# design.net
KiCad netlist of a schematic drawn in Altium Designer
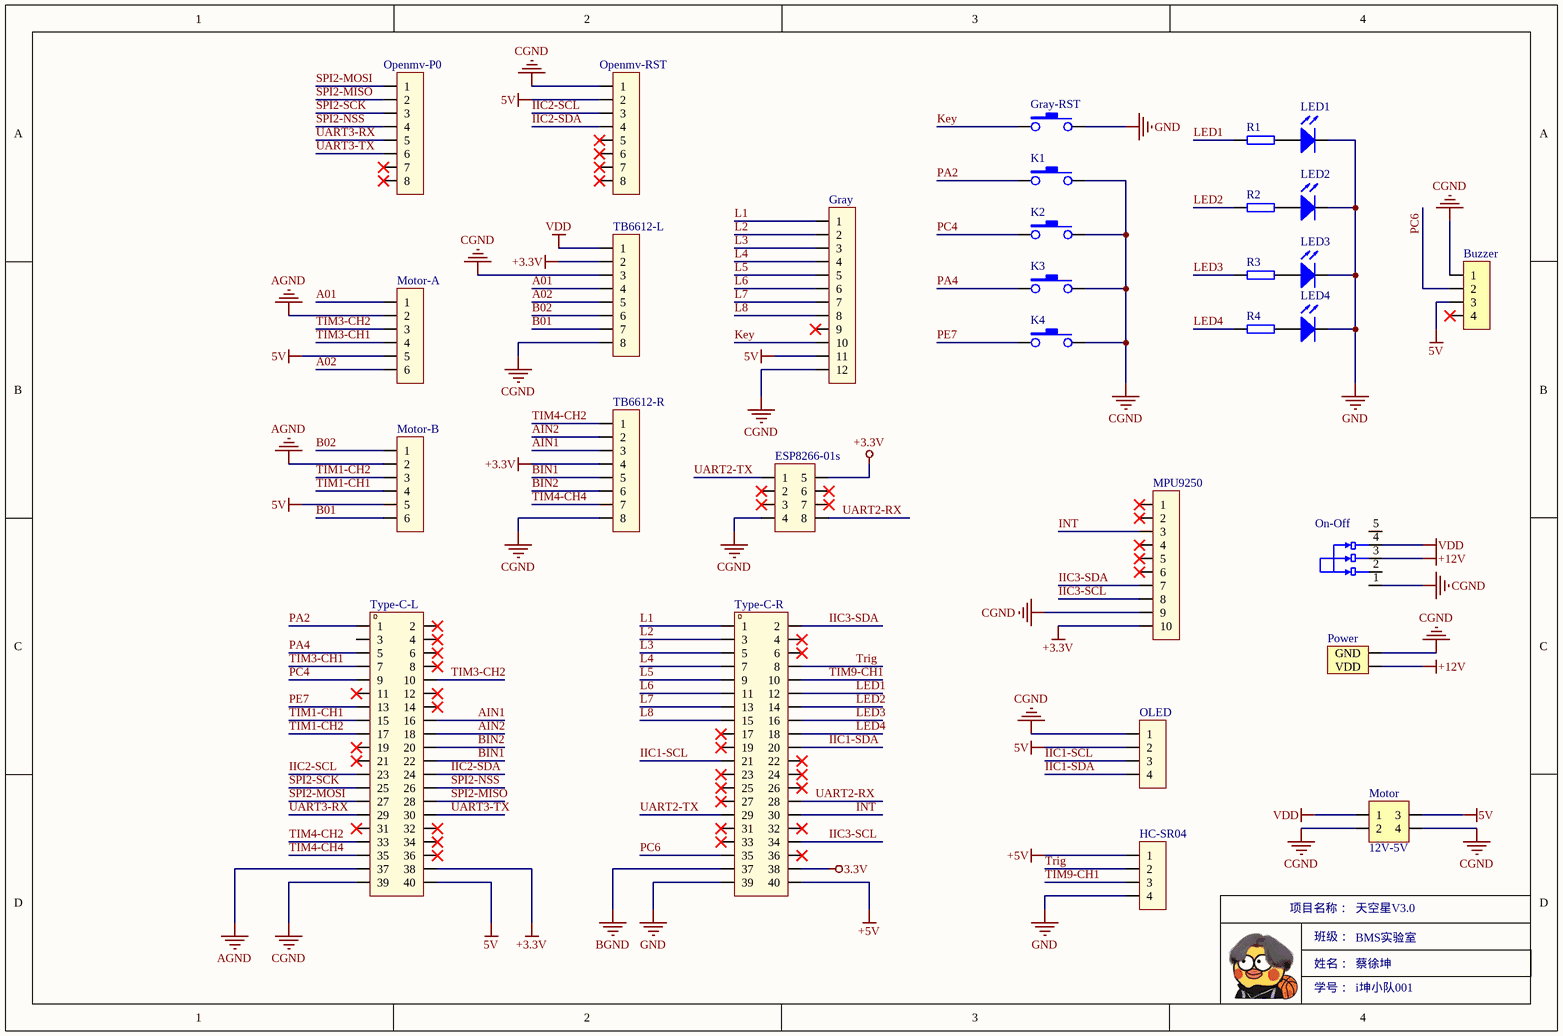
[diagram p0: 原理图.SchDoc]

(export (version "E")
  (design (tool "Eeschema 10.0.6"))
  (components
    (comp (ref "Buzzer")
      (value "~")
      (footprint "HDR2.54-M-LI-4P")
      (description "4P接插件")
      (fields (field (name "版权归属") "源创客"))
      (libsource (lib "HIST_SIE_E20240723") (part "Header 4"))
    )
    (comp (ref "ESP8266-01s")
      (value "~")
      (footprint "ESP8266-01s")
      (description "2*4P排母")
      (libsource (lib "WLOP_Yang") (part "2*4P"))
    )
    (comp (ref "Gray")
      (value "~")
      (footprint "XH2.54-1*12P")
      (description "1*12P排母")
      (libsource (lib "WLOP_Yang") (part "1*12P"))
    )
    (comp (ref "Gray-RST")
      (value "~")
      (footprint "贴片按键8mm")
      (description "12x12按键")
      (libsource (lib "HIST_SIE_E20240723") (part "Button-12X12-pin2"))
    )
    (comp (ref "HC-SR04")
      (value "~")
      (footprint "HC-SR04")
      (description "1*4P排母")
      (libsource (lib "WLOP_Yang") (part "1*4P"))
    )
    (comp (ref "K1")
      (value "~")
      (footprint "贴片按键8mm")
      (description "12x12按键")
      (libsource (lib "HIST_SIE_E20240723") (part "Button-12X12-pin2"))
    )
    (comp (ref "K2")
      (value "~")
      (footprint "贴片按键8mm")
      (description "12x12按键")
      (libsource (lib "HIST_SIE_E20240723") (part "Button-12X12-pin2"))
    )
    (comp (ref "K3")
      (value "~")
      (footprint "贴片按键8mm")
      (description "12x12按键")
      (libsource (lib "HIST_SIE_E20240723") (part "Button-12X12-pin2"))
    )
    (comp (ref "K4")
      (value "~")
      (footprint "贴片按键8mm")
      (description "12x12按键")
      (libsource (lib "HIST_SIE_E20240723") (part "Button-12X12-pin2"))
    )
    (comp (ref "LED1")
      (value "~")
      (footprint "LED-3mm")
      (description "普通M3发光二极管")
      (libsource (lib "HIST_SIE_E20240723") (part "D-LED-M3"))
    )
    (comp (ref "LED2")
      (value "~")
      (footprint "LED-3mm")
      (description "普通M3发光二极管")
      (libsource (lib "HIST_SIE_E20240723") (part "D-LED-M3"))
    )
    (comp (ref "LED3")
      (value "~")
      (footprint "LED-3mm")
      (description "普通M3发光二极管")
      (libsource (lib "HIST_SIE_E20240723") (part "D-LED-M3"))
    )
    (comp (ref "LED4")
      (value "~")
      (footprint "LED-3mm")
      (description "普通M3发光二极管")
      (libsource (lib "HIST_SIE_E20240723") (part "D-LED-M3"))
    )
    (comp (ref "Motor")
      (value "12V-5V")
      (footprint "12V-5V-Blue")
      (description "降压模块12V转5V")
      (libsource (lib "WLOP_Yang") (part "12V转5V"))
    )
    (comp (ref "Motor-A")
      (value "~")
      (footprint "XH2.54-1*6P直")
      (description "1*6P排母")
      (libsource (lib "WLOP_Yang") (part "1*6P"))
    )
    (comp (ref "Motor-B")
      (value "~")
      (footprint "XH2.54-1*6P直")
      (description "1*6P排母")
      (libsource (lib "WLOP_Yang") (part "1*6P"))
    )
    (comp (ref "MPU9250")
      (value "~")
      (footprint "MPU9250")
      (description "1*10P排母")
      (libsource (lib "WLOP_Yang") (part "1*10P"))
    )
    (comp (ref "OLED")
      (value "~")
      (footprint "OLED")
      (description "1*4P排母")
      (libsource (lib "WLOP_Yang") (part "1*4P"))
    )
    (comp (ref "On-Off")
      (value "~")
      (footprint "拨动开关")
      (description "2.54mm间距，拨动开关")
      (libsource (lib "WLOP_Yang") (part "拨动开关"))
    )
    (comp (ref "Openmv-P0")
      (value "~")
      (footprint "XH2.54-1*8P")
      (description "1*8P排母")
      (libsource (lib "WLOP_Yang") (part "1*8P"))
    )
    (comp (ref "Openmv-RST")
      (value "~")
      (footprint "XH2.54-1*8P")
      (description "1*8P排母")
      (libsource (lib "WLOP_Yang") (part "1*8P"))
    )
    (comp (ref "Power")
      (value "~")
      (footprint "立插端子-2P")
      (description "电源引脚")
      (libsource (lib "HIST_SIE_E20240723") (part "Power"))
    )
    (comp (ref "R1")
      (value "~")
      (footprint "120Ω")
      (description "1206")
      (libsource (lib "HIST_SIE_E20240723") (part "R-0805"))
    )
    (comp (ref "R2")
      (value "~")
      (footprint "120Ω")
      (description "1206")
      (libsource (lib "HIST_SIE_E20240723") (part "R-0805"))
    )
    (comp (ref "R3")
      (value "~")
      (footprint "120Ω")
      (description "1206")
      (libsource (lib "HIST_SIE_E20240723") (part "R-0805"))
    )
    (comp (ref "R4")
      (value "~")
      (footprint "120Ω")
      (description "1206")
      (libsource (lib "HIST_SIE_E20240723") (part "R-0805"))
    )
    (comp (ref "TB6612-L")
      (value "~")
      (footprint "排母-1*8P")
      (description "1*8P排母")
      (libsource (lib "WLOP_Yang") (part "1*8P"))
    )
    (comp (ref "TB6612-R")
      (value "~")
      (footprint "排母-1*8P")
      (description "1*8P排母")
      (libsource (lib "WLOP_Yang") (part "1*8P"))
    )
    (comp (ref "Type-C-L")
      (value "~")
      (footprint "排母2*20P")
      (description "2*20P排母")
      (libsource (lib "WLOP_Yang") (part "2*20P"))
    )
    (comp (ref "Type-C-R")
      (value "~")
      (footprint "排母2*20P")
      (description "2*20P排母")
      (libsource (lib "WLOP_Yang") (part "2*20P"))
    )
  )
  (nets
    (net (code "1") (name "+3.3V") (class "Default")
      (node (ref "ESP8266-01s") (pin "5") (pinfunction "5_5") (pintype "passive"))
      (node (ref "MPU9250") (pin "10") (pinfunction "10_10") (pintype "passive"))
      (node (ref "TB6612-L") (pin "2") (pinfunction "2_2") (pintype "passive"))
      (node (ref "TB6612-R") (pin "4") (pinfunction "4_4") (pintype "passive"))
      (node (ref "Type-C-L") (pin "38") (pinfunction "38_38") (pintype "passive"))
    )
    (net (code "2") (name "+5V") (class "Default")
      (node (ref "HC-SR04") (pin "1") (pinfunction "1_1") (pintype "passive"))
      (node (ref "Type-C-R") (pin "40") (pinfunction "40_40") (pintype "passive"))
    )
    (net (code "3") (name "+12V") (class "Default")
      (node (ref "On-Off") (pin "3") (pinfunction "3_3") (pintype "passive"))
      (node (ref "Power") (pin "1") (pinfunction "VDD_1") (pintype "passive"))
    )
    (net (code "4") (name "/A01") (class "Default")
      (node (ref "Motor-A") (pin "1") (pinfunction "1_1") (pintype "passive"))
      (node (ref "TB6612-L") (pin "4") (pinfunction "4_4") (pintype "passive"))
    )
    (net (code "5") (name "/A02") (class "Default")
      (node (ref "Motor-A") (pin "6") (pinfunction "6_6") (pintype "passive"))
      (node (ref "TB6612-L") (pin "5") (pinfunction "5_5") (pintype "passive"))
    )
    (net (code "6") (name "/AIN1") (class "Default")
      (node (ref "TB6612-R") (pin "3") (pinfunction "3_3") (pintype "passive"))
      (node (ref "Type-C-L") (pin "16") (pinfunction "16_16") (pintype "passive"))
    )
    (net (code "7") (name "/AIN2") (class "Default")
      (node (ref "TB6612-R") (pin "2") (pinfunction "2_2") (pintype "passive"))
      (node (ref "Type-C-L") (pin "18") (pinfunction "18_18") (pintype "passive"))
    )
    (net (code "8") (name "/B01") (class "Default")
      (node (ref "Motor-B") (pin "6") (pinfunction "6_6") (pintype "passive"))
      (node (ref "TB6612-L") (pin "7") (pinfunction "7_7") (pintype "passive"))
    )
    (net (code "9") (name "/B02") (class "Default")
      (node (ref "Motor-B") (pin "1") (pinfunction "1_1") (pintype "passive"))
      (node (ref "TB6612-L") (pin "6") (pinfunction "6_6") (pintype "passive"))
    )
    (net (code "10") (name "/BIN1") (class "Default")
      (node (ref "TB6612-R") (pin "5") (pinfunction "5_5") (pintype "passive"))
      (node (ref "Type-C-L") (pin "22") (pinfunction "22_22") (pintype "passive"))
    )
    (net (code "11") (name "/BIN2") (class "Default")
      (node (ref "TB6612-R") (pin "6") (pinfunction "6_6") (pintype "passive"))
      (node (ref "Type-C-L") (pin "20") (pinfunction "20_20") (pintype "passive"))
    )
    (net (code "12") (name "/IIC1-SCL") (class "Default")
      (node (ref "OLED") (pin "3") (pinfunction "3_3") (pintype "passive"))
      (node (ref "Type-C-R") (pin "21") (pinfunction "21_21") (pintype "passive"))
    )
    (net (code "13") (name "/IIC1-SDA") (class "Default")
      (node (ref "OLED") (pin "4") (pinfunction "4_4") (pintype "passive"))
      (node (ref "Type-C-R") (pin "20") (pinfunction "20_20") (pintype "passive"))
    )
    (net (code "14") (name "/IIC2-SCL") (class "Default")
      (node (ref "Openmv-RST") (pin "3") (pinfunction "3_3") (pintype "passive"))
      (node (ref "Type-C-L") (pin "23") (pinfunction "23_23") (pintype "passive"))
    )
    (net (code "15") (name "/IIC2-SDA") (class "Default")
      (node (ref "Openmv-RST") (pin "4") (pinfunction "4_4") (pintype "passive"))
      (node (ref "Type-C-L") (pin "24") (pinfunction "24_24") (pintype "passive"))
    )
    (net (code "16") (name "/IIC3-SCL") (class "Default")
      (node (ref "MPU9250") (pin "8") (pinfunction "8_8") (pintype "passive"))
      (node (ref "Type-C-R") (pin "34") (pinfunction "34_34") (pintype "passive"))
    )
    (net (code "17") (name "/IIC3-SDA") (class "Default")
      (node (ref "MPU9250") (pin "7") (pinfunction "7_7") (pintype "passive"))
      (node (ref "Type-C-R") (pin "2") (pinfunction "2_2") (pintype "passive"))
    )
    (net (code "18") (name "/INT") (class "Default")
      (node (ref "MPU9250") (pin "3") (pinfunction "3_3") (pintype "passive"))
      (node (ref "Type-C-R") (pin "30") (pinfunction "30_30") (pintype "passive"))
    )
    (net (code "19") (name "/Key") (class "Default")
      (node (ref "Gray") (pin "10") (pinfunction "10_10") (pintype "passive"))
      (node (ref "Gray-RST") (pin "1") (pintype "passive"))
    )
    (net (code "20") (name "/L1") (class "Default")
      (node (ref "Gray") (pin "1") (pinfunction "1_1") (pintype "passive"))
      (node (ref "Type-C-R") (pin "1") (pinfunction "1_1") (pintype "passive"))
    )
    (net (code "21") (name "/L2") (class "Default")
      (node (ref "Gray") (pin "2") (pinfunction "2_2") (pintype "passive"))
      (node (ref "Type-C-R") (pin "3") (pinfunction "3_3") (pintype "passive"))
    )
    (net (code "22") (name "/L3") (class "Default")
      (node (ref "Gray") (pin "3") (pinfunction "3_3") (pintype "passive"))
      (node (ref "Type-C-R") (pin "5") (pinfunction "5_5") (pintype "passive"))
    )
    (net (code "23") (name "/L4") (class "Default")
      (node (ref "Gray") (pin "4") (pinfunction "4_4") (pintype "passive"))
      (node (ref "Type-C-R") (pin "7") (pinfunction "7_7") (pintype "passive"))
    )
    (net (code "24") (name "/L5") (class "Default")
      (node (ref "Gray") (pin "5") (pinfunction "5_5") (pintype "passive"))
      (node (ref "Type-C-R") (pin "9") (pinfunction "9_9") (pintype "passive"))
    )
    (net (code "25") (name "/L6") (class "Default")
      (node (ref "Gray") (pin "6") (pinfunction "6_6") (pintype "passive"))
      (node (ref "Type-C-R") (pin "11") (pinfunction "11_11") (pintype "passive"))
    )
    (net (code "26") (name "/L7") (class "Default")
      (node (ref "Gray") (pin "7") (pinfunction "7_7") (pintype "passive"))
      (node (ref "Type-C-R") (pin "13") (pinfunction "13_13") (pintype "passive"))
    )
    (net (code "27") (name "/L8") (class "Default")
      (node (ref "Gray") (pin "8") (pinfunction "8_8") (pintype "passive"))
      (node (ref "Type-C-R") (pin "15") (pinfunction "15_15") (pintype "passive"))
    )
    (net (code "28") (name "/LED1") (class "Default")
      (node (ref "R1") (pin "1") (pintype "passive"))
      (node (ref "Type-C-R") (pin "12") (pinfunction "12_12") (pintype "passive"))
    )
    (net (code "29") (name "/LED2") (class "Default")
      (node (ref "R2") (pin "1") (pintype "passive"))
      (node (ref "Type-C-R") (pin "14") (pinfunction "14_14") (pintype "passive"))
    )
    (net (code "30") (name "/LED3") (class "Default")
      (node (ref "R3") (pin "1") (pintype "passive"))
      (node (ref "Type-C-R") (pin "16") (pinfunction "16_16") (pintype "passive"))
    )
    (net (code "31") (name "/LED4") (class "Default")
      (node (ref "R4") (pin "1") (pintype "passive"))
      (node (ref "Type-C-R") (pin "18") (pinfunction "18_18") (pintype "passive"))
    )
    (net (code "32") (name "/PA2") (class "Default")
      (node (ref "K1") (pin "1") (pintype "passive"))
      (node (ref "Type-C-L") (pin "1") (pinfunction "1_1") (pintype "passive"))
    )
    (net (code "33") (name "/PA4") (class "Default")
      (node (ref "K3") (pin "1") (pintype "passive"))
      (node (ref "Type-C-L") (pin "5") (pinfunction "5_5") (pintype "passive"))
    )
    (net (code "34") (name "/PC4") (class "Default")
      (node (ref "K2") (pin "1") (pintype "passive"))
      (node (ref "Type-C-L") (pin "9") (pinfunction "9_9") (pintype "passive"))
    )
    (net (code "35") (name "/PC6") (class "Default")
      (node (ref "Buzzer") (pin "2") (pinfunction "2_2") (pintype "passive"))
      (node (ref "Type-C-R") (pin "35") (pinfunction "35_35") (pintype "passive"))
    )
    (net (code "36") (name "/PE7") (class "Default")
      (node (ref "K4") (pin "1") (pintype "passive"))
      (node (ref "Type-C-L") (pin "13") (pinfunction "13_13") (pintype "passive"))
    )
    (net (code "37") (name "/SPI2-MISO") (class "Default")
      (node (ref "Openmv-P0") (pin "2") (pinfunction "2_2") (pintype "passive"))
      (node (ref "Type-C-L") (pin "28") (pinfunction "28_28") (pintype "passive"))
    )
    (net (code "38") (name "/SPI2-MOSI") (class "Default")
      (node (ref "Openmv-P0") (pin "1") (pinfunction "1_1") (pintype "passive"))
      (node (ref "Type-C-L") (pin "27") (pinfunction "27_27") (pintype "passive"))
    )
    (net (code "39") (name "/SPI2-NSS") (class "Default")
      (node (ref "Openmv-P0") (pin "4") (pinfunction "4_4") (pintype "passive"))
      (node (ref "Type-C-L") (pin "26") (pinfunction "26_26") (pintype "passive"))
    )
    (net (code "40") (name "/SPI2-SCK") (class "Default")
      (node (ref "Openmv-P0") (pin "3") (pinfunction "3_3") (pintype "passive"))
      (node (ref "Type-C-L") (pin "25") (pinfunction "25_25") (pintype "passive"))
    )
    (net (code "41") (name "/TIM1-CH1") (class "Default")
      (node (ref "Motor-B") (pin "4") (pinfunction "4_4") (pintype "passive"))
      (node (ref "Type-C-L") (pin "15") (pinfunction "15_15") (pintype "passive"))
    )
    (net (code "42") (name "/TIM1-CH2") (class "Default")
      (node (ref "Motor-B") (pin "3") (pinfunction "3_3") (pintype "passive"))
      (node (ref "Type-C-L") (pin "17") (pinfunction "17_17") (pintype "passive"))
    )
    (net (code "43") (name "/TIM3-CH1") (class "Default")
      (node (ref "Motor-A") (pin "4") (pinfunction "4_4") (pintype "passive"))
      (node (ref "Type-C-L") (pin "7") (pinfunction "7_7") (pintype "passive"))
    )
    (net (code "44") (name "/TIM3-CH2") (class "Default")
      (node (ref "Motor-A") (pin "3") (pinfunction "3_3") (pintype "passive"))
      (node (ref "Type-C-L") (pin "10") (pinfunction "10_10") (pintype "passive"))
    )
    (net (code "45") (name "/TIM4-CH2") (class "Default")
      (node (ref "TB6612-R") (pin "1") (pinfunction "1_1") (pintype "passive"))
      (node (ref "Type-C-L") (pin "33") (pinfunction "33_33") (pintype "passive"))
    )
    (net (code "46") (name "/TIM4-CH4") (class "Default")
      (node (ref "TB6612-R") (pin "7") (pinfunction "7_7") (pintype "passive"))
      (node (ref "Type-C-L") (pin "35") (pinfunction "35_35") (pintype "passive"))
    )
    (net (code "47") (name "/TIM9-CH1") (class "Default")
      (node (ref "HC-SR04") (pin "3") (pinfunction "3_3") (pintype "passive"))
      (node (ref "Type-C-R") (pin "10") (pinfunction "10_10") (pintype "passive"))
    )
    (net (code "48") (name "/Trig") (class "Default")
      (node (ref "HC-SR04") (pin "2") (pinfunction "2_2") (pintype "passive"))
      (node (ref "Type-C-R") (pin "8") (pinfunction "8_8") (pintype "passive"))
    )
    (net (code "49") (name "/UART2-RX") (class "Default")
      (node (ref "ESP8266-01s") (pin "8") (pinfunction "8_8") (pintype "passive"))
      (node (ref "Type-C-R") (pin "28") (pinfunction "28_28") (pintype "passive"))
    )
    (net (code "50") (name "/UART2-TX") (class "Default")
      (node (ref "ESP8266-01s") (pin "1") (pinfunction "1_1") (pintype "passive"))
      (node (ref "Type-C-R") (pin "29") (pinfunction "29_29") (pintype "passive"))
    )
    (net (code "51") (name "/UART3-RX") (class "Default")
      (node (ref "Openmv-P0") (pin "5") (pinfunction "5_5") (pintype "passive"))
      (node (ref "Type-C-L") (pin "29") (pinfunction "29_29") (pintype "passive"))
    )
    (net (code "52") (name "/UART3-TX") (class "Default")
      (node (ref "Openmv-P0") (pin "6") (pinfunction "6_6") (pintype "passive"))
      (node (ref "Type-C-L") (pin "30") (pinfunction "30_30") (pintype "passive"))
    )
    (net (code "53") (name "3.3V") (class "Default")
      (node (ref "Type-C-R") (pin "38") (pinfunction "38_38") (pintype "passive"))
    )
    (net (code "54") (name "5V") (class "Default")
      (node (ref "Buzzer") (pin "3") (pinfunction "3_3") (pintype "passive"))
      (node (ref "Gray") (pin "11") (pinfunction "11_11") (pintype "passive"))
      (node (ref "Motor") (pin "3") (pinfunction "3_3") (pintype "passive"))
      (node (ref "Motor-A") (pin "5") (pinfunction "5_5") (pintype "passive"))
      (node (ref "Motor-B") (pin "5") (pinfunction "5_5") (pintype "passive"))
      (node (ref "OLED") (pin "2") (pinfunction "2_2") (pintype "passive"))
      (node (ref "Openmv-RST") (pin "2") (pinfunction "2_2") (pintype "passive"))
      (node (ref "Type-C-L") (pin "40") (pinfunction "40_40") (pintype "passive"))
    )
    (net (code "55") (name "AGND") (class "Default")
      (node (ref "Motor-A") (pin "2") (pinfunction "2_2") (pintype "passive"))
      (node (ref "Motor-B") (pin "2") (pinfunction "2_2") (pintype "passive"))
      (node (ref "Type-C-L") (pin "37") (pinfunction "37_37") (pintype "passive"))
    )
    (net (code "56") (name "BGND") (class "Default")
      (node (ref "Type-C-R") (pin "37") (pinfunction "37_37") (pintype "passive"))
    )
    (net (code "57") (name "CGND") (class "Default")
      (node (ref "Buzzer") (pin "1") (pinfunction "1_1") (pintype "passive"))
      (node (ref "ESP8266-01s") (pin "4") (pinfunction "4_4") (pintype "passive"))
      (node (ref "Gray") (pin "12") (pinfunction "12_12") (pintype "passive"))
      (node (ref "K1") (pin "2") (pintype "passive"))
      (node (ref "K2") (pin "2") (pintype "passive"))
      (node (ref "K3") (pin "2") (pintype "passive"))
      (node (ref "K4") (pin "2") (pintype "passive"))
      (node (ref "MPU9250") (pin "9") (pinfunction "9_9") (pintype "passive"))
      (node (ref "Motor") (pin "2") (pinfunction "2_2") (pintype "passive"))
      (node (ref "Motor") (pin "4") (pinfunction "4_4") (pintype "passive"))
      (node (ref "OLED") (pin "1") (pinfunction "1_1") (pintype "passive"))
      (node (ref "On-Off") (pin "1") (pinfunction "1_1") (pintype "passive"))
      (node (ref "Openmv-RST") (pin "1") (pinfunction "1_1") (pintype "passive"))
      (node (ref "Power") (pin "2") (pinfunction "GND_2") (pintype "passive"))
      (node (ref "TB6612-L") (pin "3") (pinfunction "3_3") (pintype "passive"))
      (node (ref "TB6612-L") (pin "8") (pinfunction "8_8") (pintype "passive"))
      (node (ref "TB6612-R") (pin "8") (pinfunction "8_8") (pintype "passive"))
      (node (ref "Type-C-L") (pin "39") (pinfunction "39_39") (pintype "passive"))
    )
    (net (code "58") (name "GND") (class "Default")
      (node (ref "Gray-RST") (pin "2") (pintype "passive"))
      (node (ref "HC-SR04") (pin "4") (pinfunction "4_4") (pintype "passive"))
      (node (ref "LED1") (pin "2") (pinfunction "K_2") (pintype "passive"))
      (node (ref "LED2") (pin "2") (pinfunction "K_2") (pintype "passive"))
      (node (ref "LED3") (pin "2") (pinfunction "K_2") (pintype "passive"))
      (node (ref "LED4") (pin "2") (pinfunction "K_2") (pintype "passive"))
      (node (ref "Type-C-R") (pin "39") (pinfunction "39_39") (pintype "passive"))
    )
    (net (code "59") (name "Net-(LED1-A)") (class "Default")
      (node (ref "LED1") (pin "1") (pinfunction "A_1") (pintype "passive"))
      (node (ref "R1") (pin "2") (pintype "passive"))
    )
    (net (code "60") (name "Net-(LED2-A)") (class "Default")
      (node (ref "LED2") (pin "1") (pinfunction "A_1") (pintype "passive"))
      (node (ref "R2") (pin "2") (pintype "passive"))
    )
    (net (code "61") (name "Net-(LED3-A)") (class "Default")
      (node (ref "LED3") (pin "1") (pinfunction "A_1") (pintype "passive"))
      (node (ref "R3") (pin "2") (pintype "passive"))
    )
    (net (code "62") (name "Net-(LED4-A)") (class "Default")
      (node (ref "LED4") (pin "1") (pinfunction "A_1") (pintype "passive"))
      (node (ref "R4") (pin "2") (pintype "passive"))
    )
    (net (code "63") (name "VDD") (class "Default")
      (node (ref "Motor") (pin "1") (pinfunction "1_1") (pintype "passive"))
      (node (ref "On-Off") (pin "4") (pinfunction "4_4") (pintype "passive"))
      (node (ref "TB6612-L") (pin "1") (pinfunction "1_1") (pintype "passive"))
    )
    (net (code "64") (name "unconnected-(Buzzer-Pad4)") (class "Default")
      (node (ref "Buzzer") (pin "4") (pinfunction "4_4") (pintype "passive+no_connect"))
    )
    (net (code "65") (name "unconnected-(ESP8266-01s-Pad2)") (class "Default")
      (node (ref "ESP8266-01s") (pin "2") (pinfunction "2_2") (pintype "passive+no_connect"))
    )
    (net (code "66") (name "unconnected-(ESP8266-01s-Pad3)") (class "Default")
      (node (ref "ESP8266-01s") (pin "3") (pinfunction "3_3") (pintype "passive+no_connect"))
    )
    (net (code "67") (name "unconnected-(ESP8266-01s-Pad6)") (class "Default")
      (node (ref "ESP8266-01s") (pin "6") (pinfunction "6_6") (pintype "passive+no_connect"))
    )
    (net (code "68") (name "unconnected-(ESP8266-01s-Pad7)") (class "Default")
      (node (ref "ESP8266-01s") (pin "7") (pinfunction "7_7") (pintype "passive+no_connect"))
    )
    (net (code "69") (name "unconnected-(Gray-Pad9)") (class "Default")
      (node (ref "Gray") (pin "9") (pinfunction "9_9") (pintype "passive+no_connect"))
    )
    (net (code "70") (name "unconnected-(MPU9250-Pad1)") (class "Default")
      (node (ref "MPU9250") (pin "1") (pinfunction "1_1") (pintype "passive+no_connect"))
    )
    (net (code "71") (name "unconnected-(MPU9250-Pad2)") (class "Default")
      (node (ref "MPU9250") (pin "2") (pinfunction "2_2") (pintype "passive+no_connect"))
    )
    (net (code "72") (name "unconnected-(MPU9250-Pad4)") (class "Default")
      (node (ref "MPU9250") (pin "4") (pinfunction "4_4") (pintype "passive+no_connect"))
    )
    (net (code "73") (name "unconnected-(MPU9250-Pad5)") (class "Default")
      (node (ref "MPU9250") (pin "5") (pinfunction "5_5") (pintype "passive+no_connect"))
    )
    (net (code "74") (name "unconnected-(MPU9250-Pad6)") (class "Default")
      (node (ref "MPU9250") (pin "6") (pinfunction "6_6") (pintype "passive+no_connect"))
    )
    (net (code "75") (name "unconnected-(On-Off-Pad2)") (class "Default")
      (node (ref "On-Off") (pin "2") (pinfunction "2_2") (pintype "passive"))
    )
    (net (code "76") (name "unconnected-(On-Off-Pad5)") (class "Default")
      (node (ref "On-Off") (pin "5") (pinfunction "5_5") (pintype "passive"))
    )
    (net (code "77") (name "unconnected-(Openmv-P0-Pad7)") (class "Default")
      (node (ref "Openmv-P0") (pin "7") (pinfunction "7_7") (pintype "passive+no_connect"))
    )
    (net (code "78") (name "unconnected-(Openmv-P0-Pad8)") (class "Default")
      (node (ref "Openmv-P0") (pin "8") (pinfunction "8_8") (pintype "passive+no_connect"))
    )
    (net (code "79") (name "unconnected-(Openmv-RST-Pad5)") (class "Default")
      (node (ref "Openmv-RST") (pin "5") (pinfunction "5_5") (pintype "passive+no_connect"))
    )
    (net (code "80") (name "unconnected-(Openmv-RST-Pad6)") (class "Default")
      (node (ref "Openmv-RST") (pin "6") (pinfunction "6_6") (pintype "passive+no_connect"))
    )
    (net (code "81") (name "unconnected-(Openmv-RST-Pad7)") (class "Default")
      (node (ref "Openmv-RST") (pin "7") (pinfunction "7_7") (pintype "passive+no_connect"))
    )
    (net (code "82") (name "unconnected-(Openmv-RST-Pad8)") (class "Default")
      (node (ref "Openmv-RST") (pin "8") (pinfunction "8_8") (pintype "passive+no_connect"))
    )
    (net (code "83") (name "unconnected-(Type-C-L-Pad2)") (class "Default")
      (node (ref "Type-C-L") (pin "2") (pinfunction "2_2") (pintype "passive+no_connect"))
    )
    (net (code "84") (name "unconnected-(Type-C-L-Pad3)") (class "Default")
      (node (ref "Type-C-L") (pin "3") (pinfunction "3_3") (pintype "passive"))
    )
    (net (code "85") (name "unconnected-(Type-C-L-Pad4)") (class "Default")
      (node (ref "Type-C-L") (pin "4") (pinfunction "4_4") (pintype "passive+no_connect"))
    )
    (net (code "86") (name "unconnected-(Type-C-L-Pad6)") (class "Default")
      (node (ref "Type-C-L") (pin "6") (pinfunction "6_6") (pintype "passive+no_connect"))
    )
    (net (code "87") (name "unconnected-(Type-C-L-Pad8)") (class "Default")
      (node (ref "Type-C-L") (pin "8") (pinfunction "8_8") (pintype "passive+no_connect"))
    )
    (net (code "88") (name "unconnected-(Type-C-L-Pad11)") (class "Default")
      (node (ref "Type-C-L") (pin "11") (pinfunction "11_11") (pintype "passive+no_connect"))
    )
    (net (code "89") (name "unconnected-(Type-C-L-Pad12)") (class "Default")
      (node (ref "Type-C-L") (pin "12") (pinfunction "12_12") (pintype "passive+no_connect"))
    )
    (net (code "90") (name "unconnected-(Type-C-L-Pad14)") (class "Default")
      (node (ref "Type-C-L") (pin "14") (pinfunction "14_14") (pintype "passive+no_connect"))
    )
    (net (code "91") (name "unconnected-(Type-C-L-Pad19)") (class "Default")
      (node (ref "Type-C-L") (pin "19") (pinfunction "19_19") (pintype "passive+no_connect"))
    )
    (net (code "92") (name "unconnected-(Type-C-L-Pad21)") (class "Default")
      (node (ref "Type-C-L") (pin "21") (pinfunction "21_21") (pintype "passive+no_connect"))
    )
    (net (code "93") (name "unconnected-(Type-C-L-Pad31)") (class "Default")
      (node (ref "Type-C-L") (pin "31") (pinfunction "31_31") (pintype "passive+no_connect"))
    )
    (net (code "94") (name "unconnected-(Type-C-L-Pad32)") (class "Default")
      (node (ref "Type-C-L") (pin "32") (pinfunction "32_32") (pintype "passive+no_connect"))
    )
    (net (code "95") (name "unconnected-(Type-C-L-Pad34)") (class "Default")
      (node (ref "Type-C-L") (pin "34") (pinfunction "34_34") (pintype "passive+no_connect"))
    )
    (net (code "96") (name "unconnected-(Type-C-L-Pad36)") (class "Default")
      (node (ref "Type-C-L") (pin "36") (pinfunction "36_36") (pintype "passive+no_connect"))
    )
    (net (code "97") (name "unconnected-(Type-C-R-Pad4)") (class "Default")
      (node (ref "Type-C-R") (pin "4") (pinfunction "4_4") (pintype "passive+no_connect"))
    )
    (net (code "98") (name "unconnected-(Type-C-R-Pad6)") (class "Default")
      (node (ref "Type-C-R") (pin "6") (pinfunction "6_6") (pintype "passive+no_connect"))
    )
    (net (code "99") (name "unconnected-(Type-C-R-Pad17)") (class "Default")
      (node (ref "Type-C-R") (pin "17") (pinfunction "17_17") (pintype "passive+no_connect"))
    )
    (net (code "100") (name "unconnected-(Type-C-R-Pad19)") (class "Default")
      (node (ref "Type-C-R") (pin "19") (pinfunction "19_19") (pintype "passive+no_connect"))
    )
    (net (code "101") (name "unconnected-(Type-C-R-Pad22)") (class "Default")
      (node (ref "Type-C-R") (pin "22") (pinfunction "22_22") (pintype "passive+no_connect"))
    )
    (net (code "102") (name "unconnected-(Type-C-R-Pad23)") (class "Default")
      (node (ref "Type-C-R") (pin "23") (pinfunction "23_23") (pintype "passive+no_connect"))
    )
    (net (code "103") (name "unconnected-(Type-C-R-Pad24)") (class "Default")
      (node (ref "Type-C-R") (pin "24") (pinfunction "24_24") (pintype "passive+no_connect"))
    )
    (net (code "104") (name "unconnected-(Type-C-R-Pad25)") (class "Default")
      (node (ref "Type-C-R") (pin "25") (pinfunction "25_25") (pintype "passive+no_connect"))
    )
    (net (code "105") (name "unconnected-(Type-C-R-Pad26)") (class "Default")
      (node (ref "Type-C-R") (pin "26") (pinfunction "26_26") (pintype "passive+no_connect"))
    )
    (net (code "106") (name "unconnected-(Type-C-R-Pad27)") (class "Default")
      (node (ref "Type-C-R") (pin "27") (pinfunction "27_27") (pintype "passive+no_connect"))
    )
    (net (code "107") (name "unconnected-(Type-C-R-Pad31)") (class "Default")
      (node (ref "Type-C-R") (pin "31") (pinfunction "31_31") (pintype "passive+no_connect"))
    )
    (net (code "108") (name "unconnected-(Type-C-R-Pad32)") (class "Default")
      (node (ref "Type-C-R") (pin "32") (pinfunction "32_32") (pintype "passive+no_connect"))
    )
    (net (code "109") (name "unconnected-(Type-C-R-Pad33)") (class "Default")
      (node (ref "Type-C-R") (pin "33") (pinfunction "33_33") (pintype "passive+no_connect"))
    )
    (net (code "110") (name "unconnected-(Type-C-R-Pad36)") (class "Default")
      (node (ref "Type-C-R") (pin "36") (pinfunction "36_36") (pintype "passive+no_connect"))
    )
  )
)
